# solar_panel_full.net
KiCad netlist of a schematic drawn in EasyEDA Pro
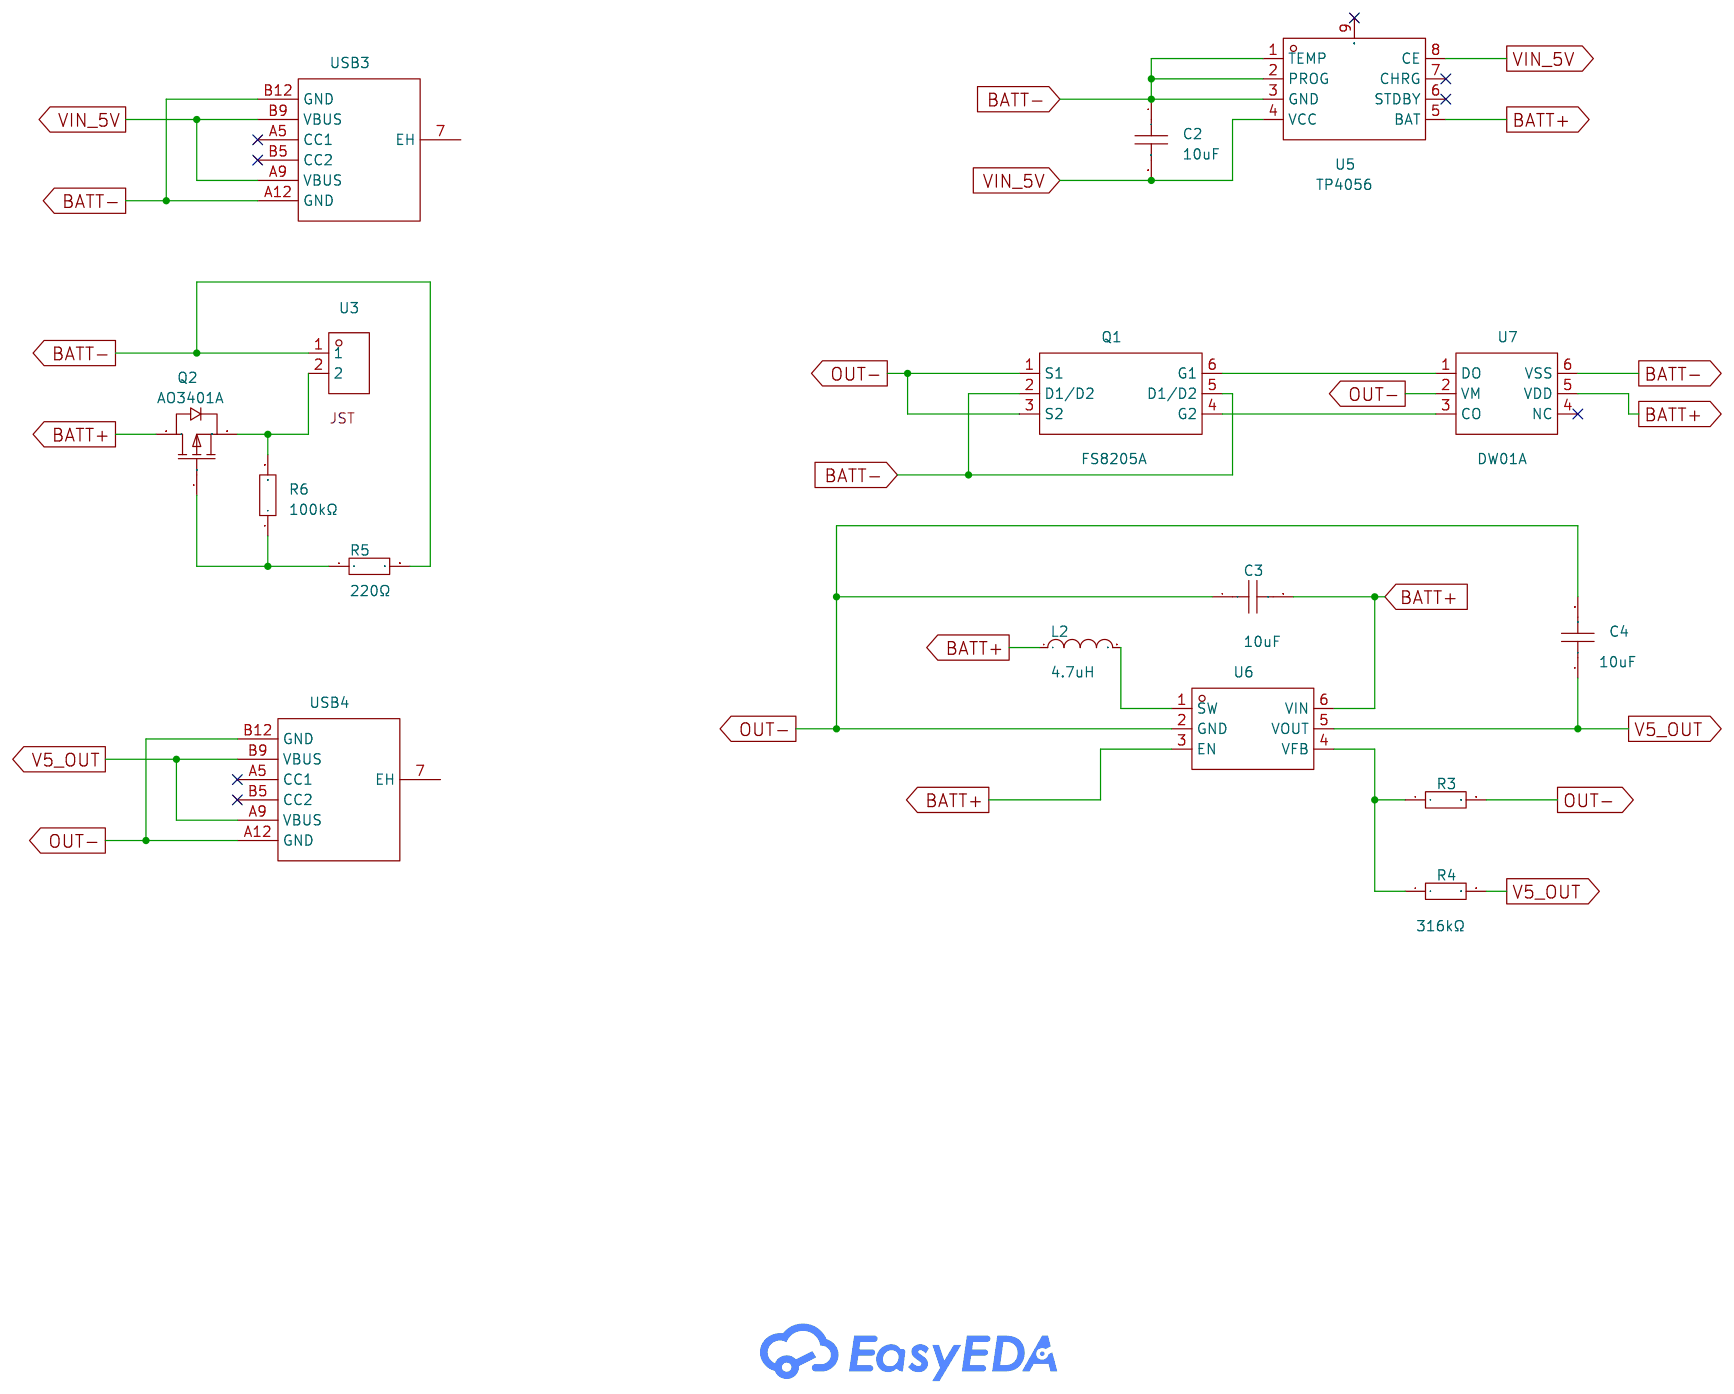
[diagram p0: schematic sheet]

(export (version "E")
  (design (tool "Eeschema 10.0.6"))
  (components
    (comp (ref "C2")
      (value "10uF")
      (footprint "easyedapro:C0603")
      (description "Capacitance:10uF Tolerance:±20% Tolerance:±20% Voltage Rating:6.3V Temperature Coefficient:X5R")
      (fields (field (name "Manufacturer Part") "C0603B106M007T") (field (name "Manufacturer") "IHHEC(禾伸堂)"))
      (libsource (lib "easyedapro") (part "CAP"))
    )
    (comp (ref "C3")
      (value "10uF")
      (footprint "easyedapro:C0603")
      (description "Capacitance:10uF Tolerance:±20% Tolerance:±20% Voltage Rating:6.3V Temperature Coefficient:X5R")
      (fields (field (name "Manufacturer Part") "C0603B106M007T") (field (name "Manufacturer") "IHHEC(禾伸堂)"))
      (libsource (lib "easyedapro") (part "CAP"))
    )
    (comp (ref "C4")
      (value "10uF")
      (footprint "easyedapro:C0603")
      (description "Capacitance:10uF Tolerance:±20% Tolerance:±20% Voltage Rating:6.3V Temperature Coefficient:X5R")
      (fields (field (name "Manufacturer Part") "C0603B106M007T") (field (name "Manufacturer") "IHHEC(禾伸堂)"))
      (libsource (lib "easyedapro") (part "CAP"))
    )
    (comp (ref "L2")
      (value "4.7uH")
      (footprint "easyedapro:L0805")
      (fields
        (field (name "Manufacturer Part") "CPY201209T-4R7M-NP")
        (field (name "Manufacturer") "Chilisin(奇力新)")
      )
      (libsource (lib "easyedapro") (part "CPY201209T-4R7M-NP"))
    )
    (comp (ref "Q1")
      (value "FS8205A")
      (footprint "easyedapro:SOT-23-6_L2.9-W1.6-P0.95-LS2.8-BR")
      (fields (field (name "Manufacturer") "FUXINSEMI(富芯森美)"))
      (libsource (lib "easyedapro") (part "FS8205A_C908265"))
    )
    (comp (ref "Q2")
      (value "AO3401A")
      (footprint "easyedapro:SOT-23_L2.9-W1.3-P1.90-LS2.4-BR")
      (fields (field (name "Manufacturer") "AOS"))
      (libsource (lib "easyedapro") (part "AO3401A"))
    )
    (comp (ref "R3")
      (value "100kΩ")
      (footprint "easyedapro:R0603")
      (fields (field (name "Manufacturer Part") "FRC0603J104 TS") (field (name "Manufacturer") "FOJAN(富捷)"))
      (libsource (lib "easyedapro") (part "Res"))
    )
    (comp (ref "R4")
      (value "316kΩ")
      (footprint "easyedapro:R0603")
      (fields (field (name "Manufacturer Part") "FRC0603F3163TS") (field (name "Manufacturer") "FOJAN(富捷)"))
      (libsource (lib "easyedapro") (part "Res"))
    )
    (comp (ref "R5")
      (value "220Ω")
      (footprint "easyedapro:R0603")
      (fields (field (name "Manufacturer Part") "SCR0603J220R") (field (name "Manufacturer") "VO(翔胜)"))
      (libsource (lib "easyedapro") (part "Res"))
    )
    (comp (ref "R6")
      (value "100kΩ")
      (footprint "easyedapro:R0603")
      (fields (field (name "Manufacturer Part") "FCR0603F100K") (field (name "Manufacturer") "VO(翔胜)"))
      (libsource (lib "easyedapro") (part "Res"))
    )
    (comp (ref "U3")
      (value "S2B-PH-SM4-TB(LF)(SN)")
      (footprint "easyedapro:CONN-TH_2P-P2.00_2B-PH-KL")
      (fields (field (name "Manufacturer") "JST"))
      (libsource (lib "easyedapro") (part "B2B-PH-KL"))
    )
    (comp (ref "U5")
      (value "TP4056")
      (footprint "easyedapro:ESOP-8_L4.9-W3.9-P1.27-LS6.0-BL-EP-4")
      (fields (field (name "Manufacturer") "YONGYUTAI(永裕泰)"))
      (libsource (lib "easyedapro") (part "TP4056_C20199357"))
    )
    (comp (ref "U6")
      (value "MCP1640BT-I/CHY")
      (footprint "easyedapro:SOT-23-6_L2.9-W1.6-P0.95-LS2.8-BR")
      (fields (field (name "Manufacturer") "MICROCHIP(美国微芯)"))
      (libsource (lib "easyedapro") (part "MCP1640BT-I/CHY"))
    )
    (comp (ref "U7")
      (value "DW01A")
      (footprint "easyedapro:SOT-23-6_L2.9-W1.6-P0.95-LS2.9-BL")
      (fields (field (name "Manufacturer") "Slkor(萨科微)"))
      (libsource (lib "easyedapro") (part "DW01A_C42380662"))
    )
    (comp (ref "USB3")
      (value "TYPE-C 6P")
      (footprint "easyedapro:TYPE-C-SMD_TYPE-C-6P_1")
      (fields (field (name "Manufacturer") "SHOU HAN(首韩)"))
      (libsource (lib "easyedapro") (part "TYPE-C 6P"))
    )
    (comp (ref "USB4")
      (value "TYPE-C 6P")
      (footprint "easyedapro:TYPE-C-SMD_TYPE-C-6P_1")
      (fields (field (name "Manufacturer") "SHOU HAN(首韩)"))
      (libsource (lib "easyedapro") (part "TYPE-C 6P"))
    )
  )
  (nets
    (net (code "1") (name "BATT+") (class "Default")
      (node (ref "C3") (pin "2") (pinfunction "2_2") (pintype "input"))
      (node (ref "L2") (pin "1") (pinfunction "1_1") (pintype "unspecified"))
      (node (ref "Q2") (pin "3") (pinfunction "D_3") (pintype "unspecified"))
      (node (ref "U5") (pin "5") (pinfunction "BAT_5") (pintype "unspecified"))
      (node (ref "U6") (pin "3") (pinfunction "EN_3") (pintype "input"))
      (node (ref "U6") (pin "6") (pinfunction "VIN_6") (pintype "input"))
      (node (ref "U7") (pin "5") (pinfunction "VDD_5") (pintype "unspecified"))
    )
    (net (code "2") (name "BATT-") (class "Default")
      (node (ref "C2") (pin "1") (pinfunction "1_1") (pintype "input"))
      (node (ref "Q1") (pin "2") (pinfunction "D1/D2_2") (pintype "unspecified"))
      (node (ref "Q1") (pin "5") (pinfunction "D1/D2_5") (pintype "unspecified"))
      (node (ref "R5") (pin "2") (pinfunction "2_2") (pintype "input"))
      (node (ref "U3") (pin "1") (pinfunction "1_1") (pintype "unspecified"))
      (node (ref "U5") (pin "1") (pinfunction "TEMP_1") (pintype "unspecified"))
      (node (ref "U5") (pin "2") (pinfunction "PROG_2") (pintype "unspecified"))
      (node (ref "U5") (pin "3") (pinfunction "GND_3") (pintype "unspecified"))
      (node (ref "U7") (pin "6") (pinfunction "VSS_6") (pintype "unspecified"))
      (node (ref "USB3") (pin "A12") (pinfunction "GND_A12") (pintype "unspecified"))
      (node (ref "USB3") (pin "B12") (pinfunction "GND_B12") (pintype "unspecified"))
    )
    (net (code "3") (name "Net-(Q1-G1)") (class "Default")
      (node (ref "Q1") (pin "6") (pinfunction "G1_6") (pintype "unspecified"))
      (node (ref "U7") (pin "1") (pinfunction "DO_1") (pintype "unspecified"))
    )
    (net (code "4") (name "Net-(Q1-G2)") (class "Default")
      (node (ref "Q1") (pin "4") (pinfunction "G2_4") (pintype "unspecified"))
      (node (ref "U7") (pin "3") (pinfunction "CO_3") (pintype "unspecified"))
    )
    (net (code "5") (name "Net-(Q2-G)") (class "Default")
      (node (ref "Q2") (pin "1") (pinfunction "G_1") (pintype "unspecified"))
      (node (ref "R5") (pin "1") (pinfunction "1_1") (pintype "input"))
      (node (ref "R6") (pin "1") (pinfunction "1_1") (pintype "input"))
    )
    (net (code "6") (name "Net-(Q2-S)") (class "Default")
      (node (ref "Q2") (pin "2") (pinfunction "S_2") (pintype "unspecified"))
      (node (ref "R6") (pin "2") (pinfunction "2_2") (pintype "input"))
      (node (ref "U3") (pin "2") (pinfunction "2_2") (pintype "unspecified"))
    )
    (net (code "7") (name "Net-(U6-SW)") (class "Default")
      (node (ref "L2") (pin "2") (pinfunction "2_2") (pintype "unspecified"))
      (node (ref "U6") (pin "1") (pinfunction "SW_1") (pintype "input"))
    )
    (net (code "8") (name "Net-(U6-VFB)") (class "Default")
      (node (ref "R3") (pin "1") (pinfunction "1_1") (pintype "input"))
      (node (ref "R4") (pin "1") (pinfunction "1_1") (pintype "input"))
      (node (ref "U6") (pin "4") (pinfunction "VFB_4") (pintype "input"))
    )
    (net (code "9") (name "OUT-") (class "Default")
      (node (ref "C3") (pin "1") (pinfunction "1_1") (pintype "input"))
      (node (ref "C4") (pin "2") (pinfunction "2_2") (pintype "input"))
      (node (ref "Q1") (pin "1") (pinfunction "S1_1") (pintype "unspecified"))
      (node (ref "Q1") (pin "3") (pinfunction "S2_3") (pintype "unspecified"))
      (node (ref "R3") (pin "2") (pinfunction "2_2") (pintype "input"))
      (node (ref "U6") (pin "2") (pinfunction "GND_2") (pintype "input"))
      (node (ref "U7") (pin "2") (pinfunction "VM_2") (pintype "unspecified"))
      (node (ref "USB4") (pin "A12") (pinfunction "GND_A12") (pintype "unspecified"))
      (node (ref "USB4") (pin "B12") (pinfunction "GND_B12") (pintype "unspecified"))
    )
    (net (code "10") (name "V5_OUT") (class "Default")
      (node (ref "C4") (pin "1") (pinfunction "1_1") (pintype "input"))
      (node (ref "R4") (pin "2") (pinfunction "2_2") (pintype "input"))
      (node (ref "U6") (pin "5") (pinfunction "VOUT_5") (pintype "input"))
      (node (ref "USB4") (pin "A9") (pinfunction "VBUS_A9") (pintype "unspecified"))
      (node (ref "USB4") (pin "B9") (pinfunction "VBUS_B9") (pintype "unspecified"))
    )
    (net (code "11") (name "VIN_5V") (class "Default")
      (node (ref "C2") (pin "2") (pinfunction "2_2") (pintype "input"))
      (node (ref "U5") (pin "4") (pinfunction "VCC_4") (pintype "unspecified"))
      (node (ref "U5") (pin "8") (pinfunction "CE_8") (pintype "unspecified"))
      (node (ref "USB3") (pin "A9") (pinfunction "VBUS_A9") (pintype "unspecified"))
      (node (ref "USB3") (pin "B9") (pinfunction "VBUS_B9") (pintype "unspecified"))
    )
    (net (code "12") (name "unconnected-(U5-CHRG-Pad7)") (class "Default")
      (node (ref "U5") (pin "7") (pinfunction "CHRG_7") (pintype "unspecified+no_connect"))
    )
    (net (code "13") (name "unconnected-(U5-PAD-Pad9)") (class "Default")
      (node (ref "U5") (pin "9") (pinfunction "PAD_9") (pintype "unspecified+no_connect"))
    )
    (net (code "14") (name "unconnected-(U5-STDBY-Pad6)") (class "Default")
      (node (ref "U5") (pin "6") (pinfunction "STDBY_6") (pintype "unspecified+no_connect"))
    )
    (net (code "15") (name "unconnected-(U7-NC-Pad4)") (class "Default")
      (node (ref "U7") (pin "4") (pinfunction "NC_4") (pintype "unspecified+no_connect"))
    )
    (net (code "16") (name "unconnected-(USB3-CC1-PadA5)") (class "Default")
      (node (ref "USB3") (pin "A5") (pinfunction "CC1_A5") (pintype "unspecified+no_connect"))
    )
    (net (code "17") (name "unconnected-(USB3-CC2-PadB5)") (class "Default")
      (node (ref "USB3") (pin "B5") (pinfunction "CC2_B5") (pintype "unspecified+no_connect"))
    )
    (net (code "18") (name "unconnected-(USB3-EH-Pad7)") (class "Default")
      (node (ref "USB3") (pin "7") (pinfunction "EH_7") (pintype "unspecified"))
    )
    (net (code "19") (name "unconnected-(USB4-CC1-PadA5)") (class "Default")
      (node (ref "USB4") (pin "A5") (pinfunction "CC1_A5") (pintype "unspecified+no_connect"))
    )
    (net (code "20") (name "unconnected-(USB4-CC2-PadB5)") (class "Default")
      (node (ref "USB4") (pin "B5") (pinfunction "CC2_B5") (pintype "unspecified+no_connect"))
    )
    (net (code "21") (name "unconnected-(USB4-EH-Pad7)") (class "Default")
      (node (ref "USB4") (pin "7") (pinfunction "EH_7") (pintype "unspecified"))
    )
  )
)
